# DIG_INTERFACES.net
KiCad netlist of a schematic drawn in Altium Designer
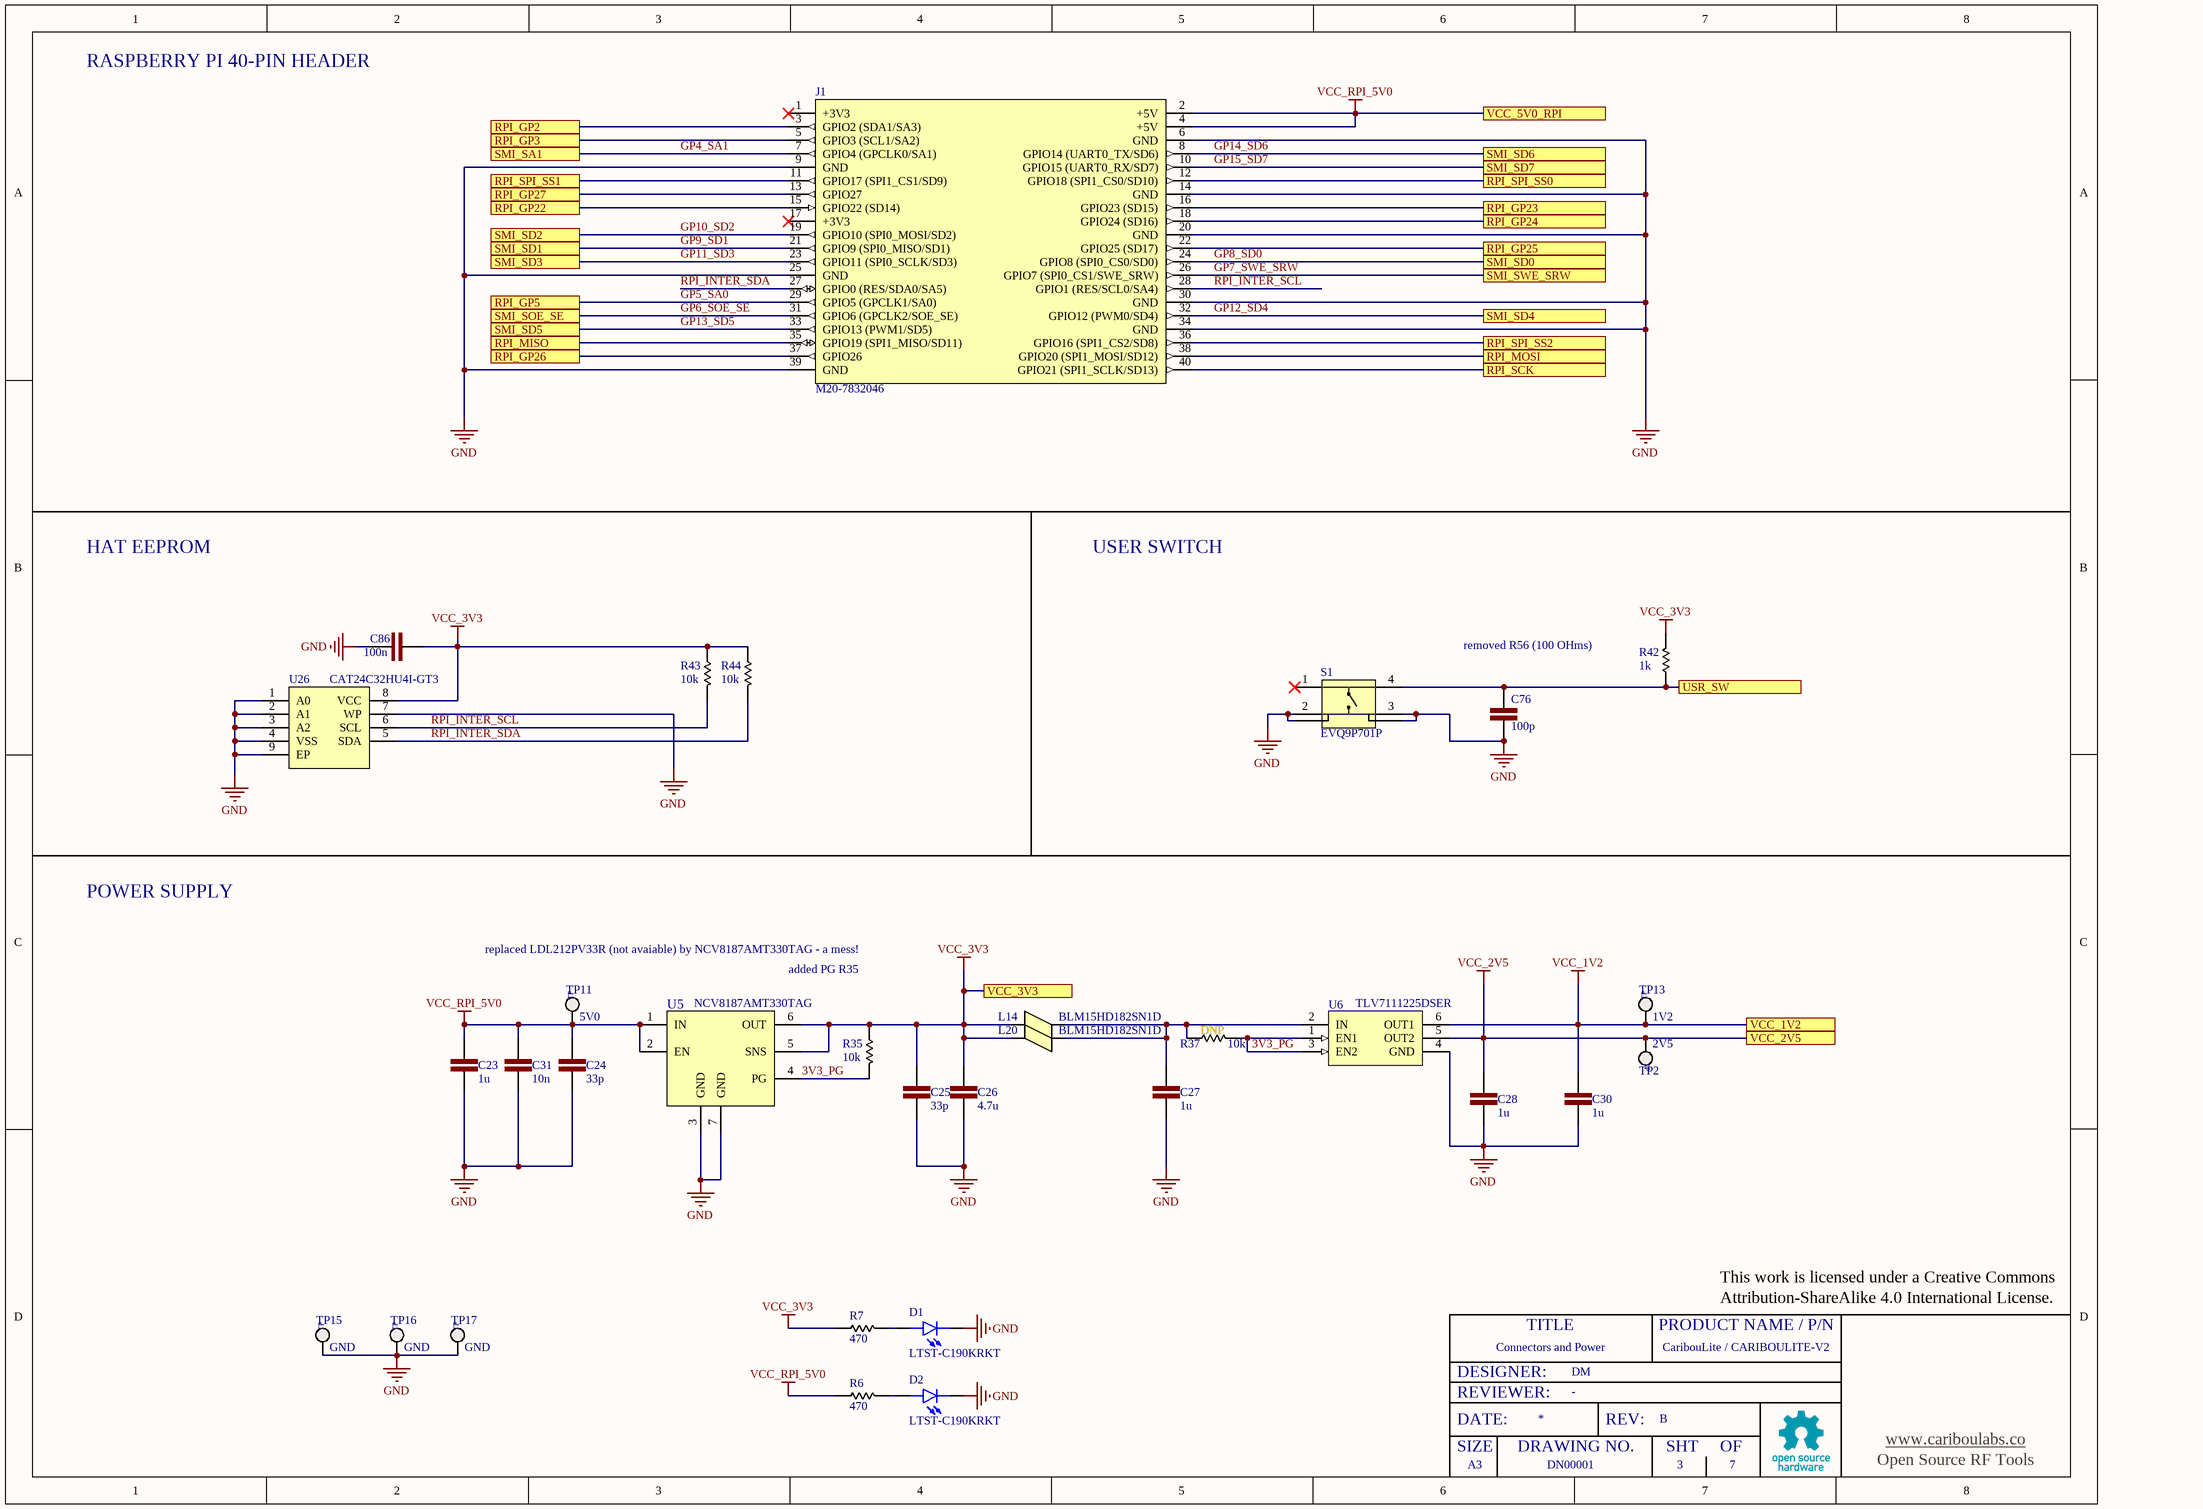
[diagram p0: DIG_INTERFACES.SchDoc]

(export (version "E")
  (design (tool "Eeschema 10.0.6"))
  (components
    (comp (ref "C23")
      (value "1u")
      (footprint "MURATA 0402")
      (description "Multilayer Ceramic Capacitors MLCC - SMD/SMT 0402 10VDC 1uF 20% X5R")
      (fields (field (name "TOLERANCE") "5%"))
      (libsource (lib "CuSiP_Lib") (part "Capacitor"))
    )
    (comp (ref "C24")
      (value "33p")
      (footprint "MURATA 0402")
      (description "Multilayer Ceramic Capacitors MLCC - SMD/SMT 0402 50V 33pF C0G 0402 5%")
      (fields (field (name "TOLERANCE") "5%"))
      (libsource (lib "") (part "Capacitor_2"))
    )
    (comp (ref "C25")
      (value "33p")
      (footprint "MURATA 0402")
      (description "Multilayer Ceramic Capacitors MLCC - SMD/SMT 0402 50V 33pF C0G 0402 5%")
      (fields (field (name "TOLERANCE") "5%"))
      (libsource (lib "") (part "Capacitor_2"))
    )
    (comp (ref "C26")
      (value "4.7u")
      (footprint "MURATA 0402")
      (description "Multilayer Ceramic Capacitors MLCC - SMD/SMT 0402 MLCC X5R 4.7 uF +/ -20% 10V")
      (fields (field (name "TOLERANCE") "20%"))
      (libsource (lib "CuSiP_Lib") (part "Capacitor"))
    )
    (comp (ref "C27")
      (value "1u")
      (footprint "MURATA 0402")
      (description "Multilayer Ceramic Capacitors MLCC - SMD/SMT 0402 10VDC 1uF 20% X5R")
      (fields (field (name "TOLERANCE") "5%"))
      (libsource (lib "CuSiP_Lib") (part "Capacitor"))
    )
    (comp (ref "C28")
      (value "1u")
      (footprint "MURATA 0402")
      (description "Multilayer Ceramic Capacitors MLCC - SMD/SMT 0402 10VDC 1uF 20% X5R")
      (fields (field (name "TOLERANCE") "5%"))
      (libsource (lib "CuSiP_Lib") (part "Capacitor"))
    )
    (comp (ref "C30")
      (value "1u")
      (footprint "MURATA 0402")
      (description "Multilayer Ceramic Capacitors MLCC - SMD/SMT 0402 10VDC 1uF 20% X5R")
      (fields (field (name "TOLERANCE") "5%"))
      (libsource (lib "CuSiP_Lib") (part "Capacitor"))
    )
    (comp (ref "C31")
      (value "10n")
      (footprint "MURATA 0402")
      (description "Multilayer Ceramic Capacitors MLCC - SMD/SMT 0402, 0.01UF 25V C0G")
      (fields (field (name "TOLERANCE") "5%"))
      (libsource (lib "") (part "Capacitor_2"))
    )
    (comp (ref "C76")
      (value "100p")
      (footprint "MURATA 0402")
      (description "Multilayer Ceramic Capacitors MLCC - SMD/SMT 50V 100pF +/-0.05")
      (fields (field (name "TOLERANCE") "0.05pF"))
      (libsource (lib "CuSiP_Lib") (part "Capacitor"))
    )
    (comp (ref "C86")
      (value "100n")
      (footprint "MURATA 0402")
      (description "Multilayer Ceramic Capacitors MLCC - SMD/SMT 16V .1uF X5R 0402 10%")
      (fields (field (name "TOLERANCE") "10%"))
      (libsource (lib "") (part "Capacitor_1"))
    )
    (comp (ref "D1")
      (value "LTST-C190KRKT")
      (footprint "LEDC1608X35N")
      (description "Red 631nm LED Indication - Discrete 2V 0603")
      (fields (field (name "MANU. P/N") "LTST-C190KRKT"))
      (libsource (lib "CuSiP_Lib") (part "LTST-C190KRKT"))
    )
    (comp (ref "D2")
      (value "LTST-C190KRKT")
      (footprint "LEDC1608X35N")
      (description "Red 631nm LED Indication - Discrete 2V 0603")
      (fields (field (name "MANU. P/N") "LTST-C190KRKT"))
      (libsource (lib "CuSiP_Lib") (part "LTST-C190KRKT"))
    )
    (comp (ref "J1")
      (value "M20-7832046")
      (footprint "rpi_zero")
      (description "RPI 40-pin 2.54mm header, 2-rows, socket")
      (libsource (lib "CuSiP_Lib") (part "RaspberryPi"))
    )
    (comp (ref "L14")
      (value "BLM15HD182SN1D")
      (footprint "0402 FERRITE BEAD")
      (description "Ferrite Beads 1800ohms GHz HiSpd")
      (fields (field (name "TOLERANCE") "25%") (field (name "MANU. P/N") "BLM15HD182SN1D"))
      (libsource (lib "CuSiP_Lib") (part "BLM15"))
    )
    (comp (ref "L20")
      (value "BLM15HD182SN1D")
      (footprint "0402 FERRITE BEAD")
      (description "Ferrite Beads 1800ohms GHz HiSpd")
      (fields (field (name "TOLERANCE") "25%") (field (name "MANU. P/N") "BLM15HD182SN1D"))
      (libsource (lib "CuSiP_Lib") (part "BLM15"))
    )
    (comp (ref "R6")
      (value "470")
      (footprint "PANASONIC 0402")
      (description "Thick Film Resistors - SMD 1/16watt 470ohms 1%")
      (fields (field (name "TOLERANCE") "1%"))
      (libsource (lib "") (part "Resistor_1"))
    )
    (comp (ref "R7")
      (value "470")
      (footprint "PANASONIC 0402")
      (description "Thick Film Resistors - SMD 1/16watt 470ohms 1%")
      (fields (field (name "TOLERANCE") "1%"))
      (libsource (lib "") (part "Resistor_1"))
    )
    (comp (ref "R35")
      (value "10k")
      (footprint "PANASONIC 0402")
      (description "Thick Film Resistors - SMD 0402 1/16watt 10Kohms 1%")
      (fields (field (name "TOLERANCE") "1%"))
      (libsource (lib "CuSiP_Lib") (part "Resistor"))
    )
    (comp (ref "R37")
      (value "10k")
      (footprint "PANASONIC 0402")
      (description "Thick Film Resistors - SMD 0402 1/16watt 10Kohms 1%")
      (fields (field (name "TOLERANCE") "1%"))
      (libsource (lib "") (part "Resistor_1"))
    )
    (comp (ref "R42")
      (value "1k")
      (footprint "PANASONIC 0402")
      (description "Thick Film Resistors - SMD 0402 1/16watt 1Kohms 1%")
      (fields (field (name "TOLERANCE") "1%"))
      (libsource (lib "") (part "Resistor_1"))
    )
    (comp (ref "R43")
      (value "10k")
      (footprint "PANASONIC 0402")
      (description "Thick Film Resistors - SMD 0402 1/16watt 10Kohms 1%")
      (fields (field (name "TOLERANCE") "1%"))
      (libsource (lib "CuSiP_Lib") (part "Resistor"))
    )
    (comp (ref "R44")
      (value "10k")
      (footprint "PANASONIC 0402")
      (description "Thick Film Resistors - SMD 0402 1/16watt 10Kohms 1%")
      (fields (field (name "TOLERANCE") "1%"))
      (libsource (lib "CuSiP_Lib") (part "Resistor"))
    )
    (comp (ref "S1")
      (value "EVQ9P701P")
      (footprint "EVQ9P701P")
      (description "Tactile Switches SMD 3.5X2.9MM SID-OP L SHAPED TERM 1.6N")
      (fields (field (name "MANU. P/N") "EVQ9P701P"))
      (libsource (lib "CuSiP_Lib") (part "EVQ9P701P"))
    )
    (comp (ref "TP2") (value "2V5") (footprint "TP_40") (libsource (lib "CuSiP_Lib") (part "TEST_POINT")))
    (comp (ref "TP11") (value "5V0") (footprint "TP_40") (libsource (lib "CuSiP_Lib") (part "TEST_POINT")))
    (comp (ref "TP13") (value "1V2") (footprint "TP_40") (libsource (lib "CuSiP_Lib") (part "TEST_POINT")))
    (comp (ref "TP15") (value "GND") (footprint "TP_40") (libsource (lib "CuSiP_Lib") (part "TEST_POINT")))
    (comp (ref "TP16") (value "GND") (footprint "TP_40") (libsource (lib "CuSiP_Lib") (part "TEST_POINT")))
    (comp (ref "TP17") (value "GND") (footprint "TP_40") (libsource (lib "CuSiP_Lib") (part "TEST_POINT")))
    (comp (ref "U5")
      (value "NCV8187AMT330TAG")
      (footprint "SON65P200X200X80-7N")
      (description "LDO Voltage Regulators 1.2A 3.3V Active discharge")
      (fields (field (name "MANU. P/N") "NCV8187AMT330TAG"))
      (libsource (lib "DM_Lib") (part "NCV8187AMT330TAG"))
    )
    (comp (ref "U6")
      (value "TLV7111225DSER")
      (footprint "SON50P150X150X80-6N")
      (description "LDO Voltage Regulators Dual 200mA Output Lo Noise Hi PSRR LDO Rg")
      (fields (field (name "MANU. P/N") "TLV7111225DSER"))
      (libsource (lib "DM_Lib") (part "TLV7111225DSER"))
    )
    (comp (ref "U26")
      (value "CAT24C32HU4I-GT3")
      (footprint "SON50P300X200X55-9N")
      (description "EEPROM Serial-I2C 32K 4Kx8 1.8V/5V UDFN8 CAT24C32HU4I-GT3")
      (fields (field (name "MANU. P/N") "CAT24C32HU4I-GT3"))
      (libsource (lib "DM_Lib") (part "CAT24C32HU4I-GT3"))
    )
  )
  (nets
    (net (code "1") (name "/3V3_PG") (class "Default")
      (node (ref "R35") (pin "2") (pinfunction "2_2") (pintype "passive"))
      (node (ref "R37") (pin "2") (pinfunction "2_2") (pintype "passive"))
      (node (ref "U5") (pin "4") (pinfunction "PG_4") (pintype "passive"))
      (node (ref "U6") (pin "1") (pinfunction "EN1_1") (pintype "input"))
      (node (ref "U6") (pin "3") (pinfunction "EN2_3") (pintype "input"))
    )
    (net (code "2") (name "/GP4_SA1") (class "Default")
      (node (ref "J1") (pin "7") (pinfunction "GPIO4_(GPCLK0/SA1)_7") (pintype "output"))
    )
    (net (code "3") (name "/GP5_SA0") (class "Default")
      (node (ref "J1") (pin "29") (pinfunction "GPIO5_(GPCLK1/SA0)_29") (pintype "output"))
    )
    (net (code "4") (name "/GP6_SOE_SE") (class "Default")
      (node (ref "J1") (pin "31") (pinfunction "GPIO6_(GPCLK2/SOE_SE)_31") (pintype "output"))
    )
    (net (code "5") (name "/GP7_SWE_SRW") (class "Default")
      (node (ref "J1") (pin "26") (pinfunction "GPIO7_(SPI0_CS1/SWE_SRW)_26") (pintype "output"))
    )
    (net (code "6") (name "/GP8_SD0") (class "Default")
      (node (ref "J1") (pin "24") (pinfunction "GPIO8_(SPI0_CS0/SD0)_24") (pintype "output"))
    )
    (net (code "7") (name "/GP9_SD1") (class "Default")
      (node (ref "J1") (pin "21") (pinfunction "GPIO9_(SPI0_MISO/SD1)_21") (pintype "output"))
    )
    (net (code "8") (name "/GP10_SD2") (class "Default")
      (node (ref "J1") (pin "19") (pinfunction "GPIO10_(SPI0_MOSI/SD2)_19") (pintype "output"))
    )
    (net (code "9") (name "/GP11_SD3") (class "Default")
      (node (ref "J1") (pin "23") (pinfunction "GPIO11_(SPI0_SCLK/SD3)_23") (pintype "output"))
    )
    (net (code "10") (name "/GP12_SD4") (class "Default")
      (node (ref "J1") (pin "32") (pinfunction "GPIO12_(PWM0/SD4)_32") (pintype "output"))
    )
    (net (code "11") (name "/GP13_SD5") (class "Default")
      (node (ref "J1") (pin "33") (pinfunction "GPIO13_(PWM1/SD5)_33") (pintype "output"))
    )
    (net (code "12") (name "/GP14_SD6") (class "Default")
      (node (ref "J1") (pin "8") (pinfunction "GPIO14_(UART0_TX/SD6)_8") (pintype "output"))
    )
    (net (code "13") (name "/GP15_SD7") (class "Default")
      (node (ref "J1") (pin "10") (pinfunction "GPIO15_(UART0_RX/SD7)_10") (pintype "output"))
    )
    (net (code "14") (name "/RPI_GP2") (class "Default")
      (node (ref "J1") (pin "3") (pinfunction "GPIO2_(SDA1/SA3)_3") (pintype "output"))
    )
    (net (code "15") (name "/RPI_GP3") (class "Default")
      (node (ref "J1") (pin "5") (pinfunction "GPIO3_(SCL1/SA2)_5") (pintype "output"))
    )
    (net (code "16") (name "/RPI_GP22") (class "Default")
      (node (ref "J1") (pin "15") (pinfunction "GPIO22_(SD14)_15") (pintype "input"))
    )
    (net (code "17") (name "/RPI_GP23") (class "Default")
      (node (ref "J1") (pin "16") (pinfunction "GPIO23_(SD15)_16") (pintype "output"))
    )
    (net (code "18") (name "/RPI_GP24") (class "Default")
      (node (ref "J1") (pin "18") (pinfunction "GPIO24_(SD16)_18") (pintype "output"))
    )
    (net (code "19") (name "/RPI_GP25") (class "Default")
      (node (ref "J1") (pin "22") (pinfunction "GPIO25_(SD17)_22") (pintype "output"))
    )
    (net (code "20") (name "/RPI_GP26") (class "Default")
      (node (ref "J1") (pin "37") (pinfunction "GPIO26_37") (pintype "output"))
    )
    (net (code "21") (name "/RPI_GP27") (class "Default")
      (node (ref "J1") (pin "13") (pinfunction "GPIO27_13") (pintype "output"))
    )
    (net (code "22") (name "/RPI_INTER_SCL") (class "Default")
      (node (ref "J1") (pin "28") (pinfunction "GPIO1_(RES/SCL0/SA4)_28") (pintype "output"))
      (node (ref "R43") (pin "2") (pinfunction "2_2") (pintype "passive"))
      (node (ref "U26") (pin "6") (pinfunction "SCL_6") (pintype "passive"))
    )
    (net (code "23") (name "/RPI_INTER_SDA") (class "Default")
      (node (ref "J1") (pin "27") (pinfunction "GPIO0_(RES/SDA0/SA5)_27") (pintype "bidirectional"))
      (node (ref "R44") (pin "2") (pinfunction "2_2") (pintype "passive"))
      (node (ref "U26") (pin "5") (pinfunction "SDA_5") (pintype "passive"))
    )
    (net (code "24") (name "/RPI_MISO") (class "Default")
      (node (ref "J1") (pin "35") (pinfunction "GPIO19_(SPI1_MISO/SD11)_35") (pintype "bidirectional"))
    )
    (net (code "25") (name "/RPI_MOSI") (class "Default")
      (node (ref "J1") (pin "38") (pinfunction "GPIO20_(SPI1_MOSI/SD12)_38") (pintype "output"))
    )
    (net (code "26") (name "/RPI_SCK") (class "Default")
      (node (ref "J1") (pin "40") (pinfunction "GPIO21_(SPI1_SCLK/SD13)_40") (pintype "output"))
    )
    (net (code "27") (name "/RPI_SPI_SS0") (class "Default")
      (node (ref "J1") (pin "12") (pinfunction "GPIO18_(SPI1_CS0/SD10)_12") (pintype "output"))
    )
    (net (code "28") (name "/RPI_SPI_SS1") (class "Default")
      (node (ref "J1") (pin "11") (pinfunction "GPIO17_(SPI1_CS1/SD9)_11") (pintype "output"))
    )
    (net (code "29") (name "/RPI_SPI_SS2") (class "Default")
      (node (ref "J1") (pin "36") (pinfunction "GPIO16_(SPI1_CS2/SD8)_36") (pintype "output"))
    )
    (net (code "30") (name "/USR_SW") (class "Default")
      (node (ref "C76") (pin "2") (pinfunction "2_2") (pintype "passive"))
      (node (ref "R42") (pin "1") (pinfunction "1_1") (pintype "passive"))
      (node (ref "S1") (pin "4") (pinfunction "4_4") (pintype "passive"))
    )
    (net (code "31") (name "GND") (class "Default")
      (node (ref "C23") (pin "1") (pinfunction "1_1") (pintype "passive"))
      (node (ref "C24") (pin "2") (pinfunction "2_2") (pintype "passive"))
      (node (ref "C25") (pin "2") (pinfunction "2_2") (pintype "passive"))
      (node (ref "C26") (pin "1") (pinfunction "1_1") (pintype "passive"))
      (node (ref "C27") (pin "1") (pinfunction "1_1") (pintype "passive"))
      (node (ref "C28") (pin "1") (pinfunction "1_1") (pintype "passive"))
      (node (ref "C30") (pin "1") (pinfunction "1_1") (pintype "passive"))
      (node (ref "C31") (pin "2") (pinfunction "2_2") (pintype "passive"))
      (node (ref "C76") (pin "1") (pinfunction "1_1") (pintype "passive"))
      (node (ref "C86") (pin "1") (pinfunction "1_1") (pintype "passive"))
      (node (ref "D1") (pin "C") (pinfunction "C_C") (pintype "passive"))
      (node (ref "D2") (pin "C") (pinfunction "C_C") (pintype "passive"))
      (node (ref "J1") (pin "14") (pinfunction "GND_14") (pintype "power_in"))
      (node (ref "J1") (pin "20") (pinfunction "GND_20") (pintype "power_in"))
      (node (ref "J1") (pin "25") (pinfunction "GND_25") (pintype "power_in"))
      (node (ref "J1") (pin "30") (pinfunction "GND_30") (pintype "power_in"))
      (node (ref "J1") (pin "34") (pinfunction "GND_34") (pintype "power_in"))
      (node (ref "J1") (pin "39") (pinfunction "GND_39") (pintype "power_in"))
      (node (ref "J1") (pin "6") (pinfunction "GND_6") (pintype "power_in"))
      (node (ref "J1") (pin "9") (pinfunction "GND_9") (pintype "power_in"))
      (node (ref "S1") (pin "2") (pinfunction "2_2") (pintype "passive"))
      (node (ref "S1") (pin "3") (pinfunction "3_3") (pintype "passive"))
      (node (ref "S1") (pin "5") (pinfunction "5_5") (pintype "passive"))
      (node (ref "S1") (pin "6") (pinfunction "6_6") (pintype "passive"))
      (node (ref "TP15") (pin "1") (pinfunction "TP_1") (pintype "passive"))
      (node (ref "TP16") (pin "1") (pinfunction "TP_1") (pintype "passive"))
      (node (ref "TP17") (pin "1") (pinfunction "TP_1") (pintype "passive"))
      (node (ref "U26") (pin "1") (pinfunction "A0_1") (pintype "passive"))
      (node (ref "U26") (pin "2") (pinfunction "A1_2") (pintype "passive"))
      (node (ref "U26") (pin "3") (pinfunction "A2_3") (pintype "passive"))
      (node (ref "U26") (pin "4") (pinfunction "VSS_4") (pintype "power_in"))
      (node (ref "U26") (pin "7") (pinfunction "WP_7") (pintype "passive"))
      (node (ref "U26") (pin "9") (pinfunction "EP_9") (pintype "power_in"))
      (node (ref "U5") (pin "3") (pinfunction "GND_3") (pintype "passive"))
      (node (ref "U5") (pin "7") (pinfunction "GND_7") (pintype "passive"))
      (node (ref "U6") (pin "4") (pinfunction "GND_4") (pintype "power_in"))
    )
    (net (code "32") (name "Net-(D1-PadA)") (class "Default")
      (node (ref "D1") (pin "A") (pinfunction "A_A") (pintype "passive"))
      (node (ref "R7") (pin "2") (pinfunction "2_2") (pintype "passive"))
    )
    (net (code "33") (name "Net-(D2-PadA)") (class "Default")
      (node (ref "D2") (pin "A") (pinfunction "A_A") (pintype "passive"))
      (node (ref "R6") (pin "2") (pinfunction "2_2") (pintype "passive"))
    )
    (net (code "34") (name "Net-(U6-IN)") (class "Default")
      (node (ref "C27") (pin "2") (pinfunction "2_2") (pintype "passive"))
      (node (ref "L14") (pin "2") (pinfunction "2_2") (pintype "passive"))
      (node (ref "L20") (pin "2") (pinfunction "2_2") (pintype "passive"))
      (node (ref "R37") (pin "1") (pinfunction "1_1") (pintype "passive"))
      (node (ref "U6") (pin "2") (pinfunction "IN_2") (pintype "power_in"))
    )
    (net (code "35") (name "VCC_1V2") (class "Default")
      (node (ref "C30") (pin "2") (pinfunction "2_2") (pintype "passive"))
      (node (ref "TP13") (pin "1") (pinfunction "TP_1") (pintype "passive"))
      (node (ref "U6") (pin "6") (pinfunction "OUT1_6") (pintype "power_in"))
    )
    (net (code "36") (name "VCC_2V5") (class "Default")
      (node (ref "C28") (pin "2") (pinfunction "2_2") (pintype "passive"))
      (node (ref "TP2") (pin "1") (pinfunction "TP_1") (pintype "passive"))
      (node (ref "U6") (pin "5") (pinfunction "OUT2_5") (pintype "power_in"))
    )
    (net (code "37") (name "VCC_3V3") (class "Default")
      (node (ref "C25") (pin "1") (pinfunction "1_1") (pintype "passive"))
      (node (ref "C26") (pin "2") (pinfunction "2_2") (pintype "passive"))
      (node (ref "C86") (pin "2") (pinfunction "2_2") (pintype "passive"))
      (node (ref "L14") (pin "1") (pinfunction "1_1") (pintype "passive"))
      (node (ref "L20") (pin "1") (pinfunction "1_1") (pintype "passive"))
      (node (ref "R35") (pin "1") (pinfunction "1_1") (pintype "passive"))
      (node (ref "R42") (pin "2") (pinfunction "2_2") (pintype "passive"))
      (node (ref "R43") (pin "1") (pinfunction "1_1") (pintype "passive"))
      (node (ref "R44") (pin "1") (pinfunction "1_1") (pintype "passive"))
      (node (ref "R7") (pin "1") (pinfunction "1_1") (pintype "passive"))
      (node (ref "U26") (pin "8") (pinfunction "VCC_8") (pintype "power_in"))
      (node (ref "U5") (pin "5") (pinfunction "SNS_5") (pintype "passive"))
      (node (ref "U5") (pin "6") (pinfunction "OUT_6") (pintype "passive"))
    )
    (net (code "38") (name "VCC_RPI_5V0") (class "Default")
      (node (ref "C23") (pin "2") (pinfunction "2_2") (pintype "passive"))
      (node (ref "C24") (pin "1") (pinfunction "1_1") (pintype "passive"))
      (node (ref "C31") (pin "1") (pinfunction "1_1") (pintype "passive"))
      (node (ref "J1") (pin "2") (pinfunction "+5V_2") (pintype "power_in"))
      (node (ref "J1") (pin "4") (pinfunction "+5V_4") (pintype "power_in"))
      (node (ref "R6") (pin "1") (pinfunction "1_1") (pintype "passive"))
      (node (ref "TP11") (pin "1") (pinfunction "TP_1") (pintype "passive"))
      (node (ref "U5") (pin "1") (pinfunction "IN_1") (pintype "passive"))
      (node (ref "U5") (pin "2") (pinfunction "EN_2") (pintype "passive"))
    )
    (net (code "39") (name "unconnected-(J1-+3V3-Pad1)") (class "Default")
      (node (ref "J1") (pin "1") (pinfunction "+3V3_1") (pintype "power_in+no_connect"))
    )
    (net (code "40") (name "unconnected-(J1-+3V3-Pad17)") (class "Default")
      (node (ref "J1") (pin "17") (pinfunction "+3V3_17") (pintype "passive+no_connect"))
    )
    (net (code "41") (name "unconnected-(S1-Pad1)") (class "Default")
      (node (ref "S1") (pin "1") (pinfunction "1_1") (pintype "passive+no_connect"))
    )
  )
)
